# MCU_test.net
KiCad netlist of a schematic drawn in Altium Designer
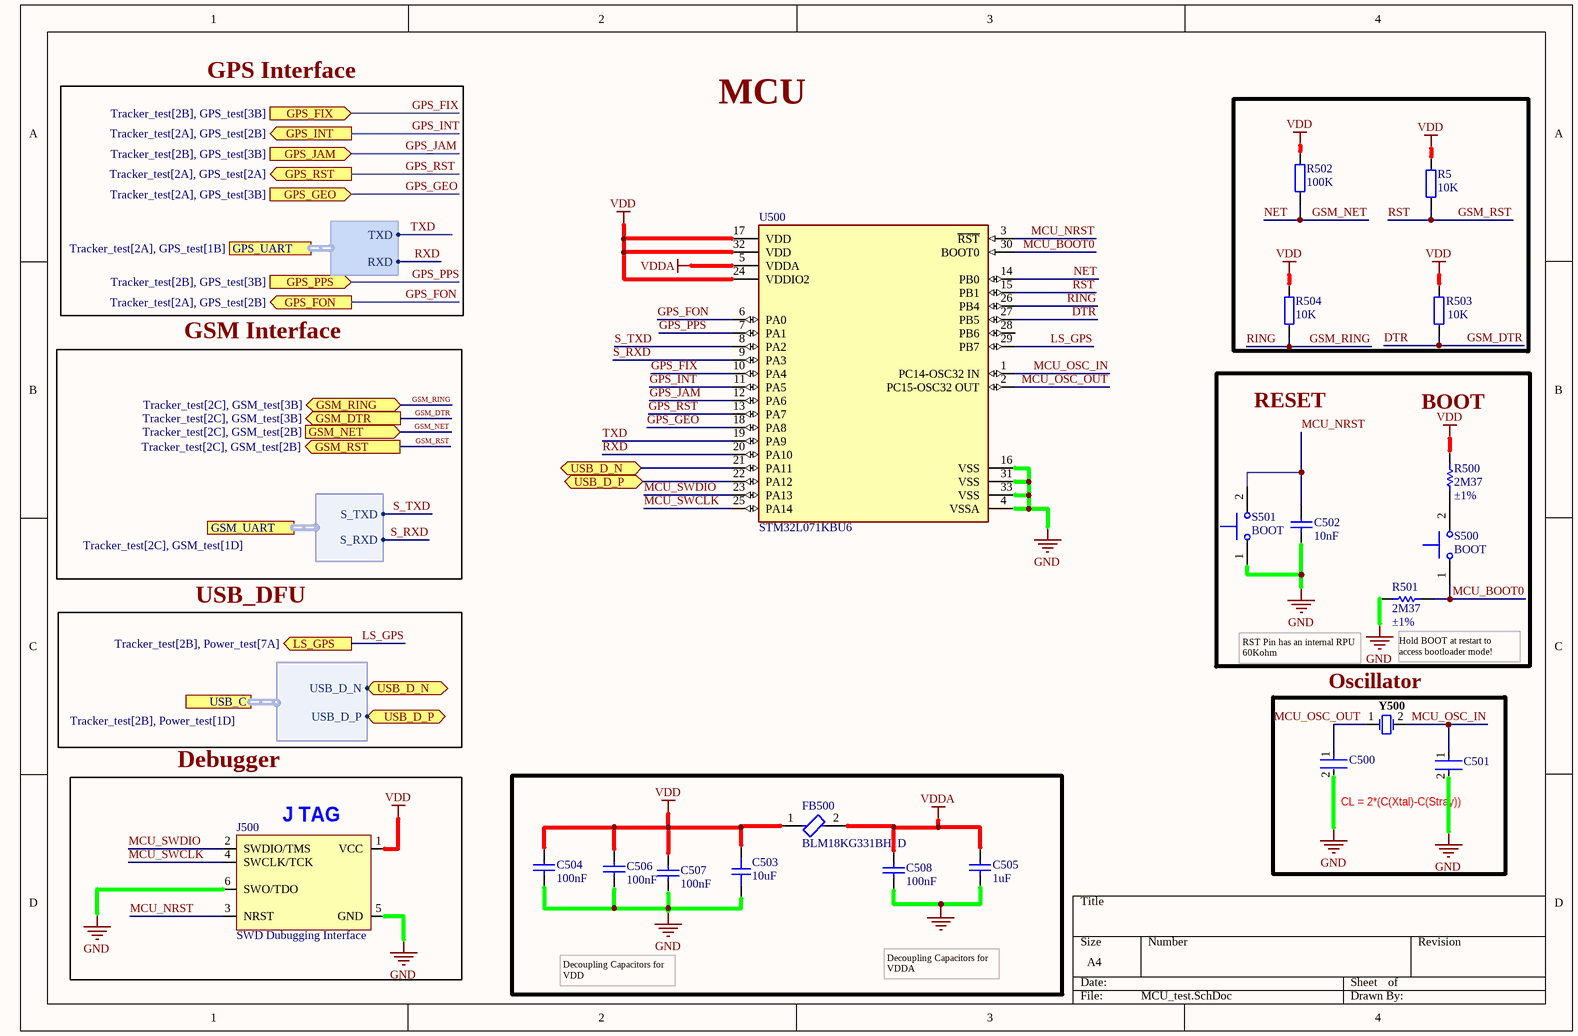
[diagram p0: MCU_test.SchDoc]

(export (version "E")
  (design (tool "Eeschema 10.0.6"))
  (components
    (comp (ref "C500")
      (value "C0603C220K5RACAUTO")
      (footprint "FP-C0603C-CF-IPC_B")
      (description "Cap Ceramic 22pF 50V X7R 10% SMD 0603 125°C Punched Paper T/R")
      (fields (field (name "TOLERANCE") "0.1") (field (name "MANUFACTURER") "KEMET"))
      (libsource (lib "intrgrat_lib") (part "CMP-03020-018041-1"))
    )
    (comp (ref "C501")
      (value "C0603C220K5RACAUTO")
      (footprint "FP-C0603C-CF-IPC_B")
      (description "Cap Ceramic 22pF 50V X7R 10% SMD 0603 125°C Punched Paper T/R")
      (fields (field (name "TOLERANCE") "0.1") (field (name "MANUFACTURER") "KEMET"))
      (libsource (lib "intrgrat_lib") (part "CMP-03020-018041-1"))
    )
    (comp (ref "C502")
      (value "10nF")
      (footprint "C0402 - duplicate")
      (description "CAP CER 0.1UF 10V X7R 0603")
      (fields
        (field (name "PART NUMBER") "C00062")
        (field (name "MANUFACTURER") "KEMET - Electronic Component")
      )
      (libsource (lib "intrgrat_lib") (part "CAP"))
    )
    (comp (ref "C503")
      (value "10uF")
      (footprint "CAP_0402")
      (description "Capacitor SMD 0402")
      (libsource (lib "PhilsLab_Library") (part "CAP_0402"))
    )
    (comp (ref "C504")
      (value "100nF")
      (footprint "C0402 - duplicate")
      (description "CAP CER 0.1UF 10V X7R 0603")
      (fields
        (field (name "PART NUMBER") "C00062")
        (field (name "MANUFACTURER") "KEMET - Electronic Component")
      )
      (libsource (lib "intrgrat_lib") (part "CAP"))
    )
    (comp (ref "C505")
      (value "1uF")
      (footprint "C0402 - duplicate")
      (description "CAP CER 0.1UF 10V X7R 0603")
      (fields
        (field (name "PART NUMBER") "C00062")
        (field (name "MANUFACTURER") "KEMET - Electronic Component")
      )
      (libsource (lib "intrgrat_lib") (part "CAP"))
    )
    (comp (ref "C506")
      (value "100nF")
      (footprint "C0402 - duplicate")
      (description "CAP CER 0.1UF 10V X7R 0603")
      (fields
        (field (name "PART NUMBER") "C00062")
        (field (name "MANUFACTURER") "KEMET - Electronic Component")
      )
      (libsource (lib "intrgrat_lib") (part "CAP"))
    )
    (comp (ref "C507")
      (value "100nF")
      (footprint "C0402 - duplicate")
      (description "CAP CER 0.1UF 10V X7R 0603")
      (fields
        (field (name "PART NUMBER") "C00062")
        (field (name "MANUFACTURER") "KEMET - Electronic Component")
      )
      (libsource (lib "intrgrat_lib") (part "CAP"))
    )
    (comp (ref "C508")
      (value "100nF")
      (footprint "C0402 - duplicate")
      (description "CAP CER 0.1UF 10V X7R 0603")
      (fields
        (field (name "PART NUMBER") "C00062")
        (field (name "MANUFACTURER") "KEMET - Electronic Component")
      )
      (libsource (lib "intrgrat_lib") (part "CAP"))
    )
    (comp (ref "FB500")
      (value "BLM18KG331BH1D")
      (footprint "FP-BLM18-0_15-t0_8-IPC_A")
      (description "Chip Ferrite Bead, 0603, 330Ω @ 100MHz, 0.08Ω, 25%, 1.2A")
      (libsource (lib "intrgrat_lib") (part "CMP-06046-002312-1"))
    )
    (comp (ref "J500")
      (value "SWD Dubugging Interface")
      (footprint "TC2030-NL-FP")
      (description "Tag-Connect No-Solder SWD Debug Connector (No Legs) DO NOT PLACE")
      (fields
        (field (name "MANUFACTURER") "Tag-Connect")
        (field (name "MANUFACTURER PART NUMBER") "TC2030-NL-FP")
      )
      (libsource (lib "intrgrat_lib") (part "TC2030-NL"))
    )
    (comp (ref "R5")
      (value "10K")
      (footprint "RES_0402")
      (description "Resistor SMD 0402")
      (libsource (lib "PhilsLab_Library") (part "RES_0402"))
    )
    (comp (ref "R500")
      (value "2M37")
      (footprint "R0402")
      (description "RES SMD 15 OHM 1% 1/10W 0603")
      (fields
        (field (name "PART NUMBER") "R00007")
        (field (name "MANUFACTURER") "Yageo")
        (field (name "TOLERANCE") "±1%")
      )
      (libsource (lib "intrgrat_lib") (part "RES"))
    )
    (comp (ref "R501")
      (value "2M37")
      (footprint "R0402")
      (description "RES SMD 15 OHM 1% 1/10W 0603")
      (fields
        (field (name "PART NUMBER") "R00007")
        (field (name "MANUFACTURER") "Yageo")
        (field (name "TOLERANCE") "±1%")
      )
      (libsource (lib "intrgrat_lib") (part "RES"))
    )
    (comp (ref "R502")
      (value "100K")
      (footprint "RES_0402")
      (description "Resistor SMD 0402")
      (libsource (lib "PhilsLab_Library") (part "RES_0402"))
    )
    (comp (ref "R503")
      (value "10K")
      (footprint "RES_0402")
      (description "Resistor SMD 0402")
      (libsource (lib "PhilsLab_Library") (part "RES_0402"))
    )
    (comp (ref "R504")
      (value "10K")
      (footprint "RES_0402")
      (description "Resistor SMD 0402")
      (libsource (lib "PhilsLab_Library") (part "RES_0402"))
    )
    (comp (ref "S500")
      (value "BOOT")
      (footprint "SW_B3U-1000P")
      (description "SWITCH TACTILE SPST-NO 0.05A 12V")
      (fields
        (field (name "PARTNUMBER") "B3U-1000P")
        (field (name "MANUFACTURER") "Omron Electronic Components")
        (field (name "SYMBOLCREATOR") "a0412235")
        (field (name "PUBLISHER") "Texas Instruments")
      )
      (libsource (lib "intrgrat_lib") (part "B3U-1000P"))
    )
    (comp (ref "S501")
      (value "BOOT")
      (footprint "SW_B3U-1000P")
      (description "SWITCH TACTILE SPST-NO 0.05A 12V")
      (fields
        (field (name "PARTNUMBER") "B3U-1000P")
        (field (name "MANUFACTURER") "Omron Electronic Components")
        (field (name "SYMBOLCREATOR") "a0412235")
        (field (name "PUBLISHER") "Texas Instruments")
      )
      (libsource (lib "intrgrat_lib") (part "B3U-1000P"))
    )
    (comp (ref "U500")
      (value "STM32L071KBU6")
      (footprint "FP-UFQFPN32-A0B8-IPC_B")
      (description "IC MCU 32BIT 128KB FLASH 32QFPN")
      (fields
        (field (name "OCTOPART") "https://octopart.com/stm32l071kbu6-stmicroelectronics-67270308")
        (field (name "MANUFACTURER") "STMicroelectronics")
      )
      (libsource (lib "intrgrat_lib") (part "CMP-12105-000059-1"))
    )
    (comp (ref "Y500")
      (value "NX3225GD-8MHZ-STD-CRA-3")
      (footprint "NDK-NX3225GD-8MHZ-STD-CRA-3_V")
      (description "Crystal Unit, 8 MHz, 8 pF, -40 to 150 degC, 2-Pin SMD, RoHS, Tape and Reel")
      (fields (field (name "MANUFACTURER") "NDK"))
      (libsource (lib "intrgrat_lib") (part "CMP-2000-07595-1"))
    )
  )
  (nets
    (net (code "4") (name "/DTR") (class "Default")
      (node (ref "R503") (pin "1") (pinfunction "1_1") (pintype "passive"))
      (node (ref "U500") (pin "27") (pinfunction "PB5_27") (pintype "bidirectional"))
    )
    (net (code "5") (name "/GPS_FIX") (class "Default")
      (node (ref "U500") (pin "10") (pinfunction "PA4_10") (pintype "bidirectional"))
    )
    (net (code "6") (name "/GPS_FON") (class "Default")
      (node (ref "U500") (pin "6") (pinfunction "PA0_6") (pintype "bidirectional"))
    )
    (net (code "7") (name "/GPS_GEO") (class "Default")
      (node (ref "U500") (pin "18") (pinfunction "PA8_18") (pintype "bidirectional"))
    )
    (net (code "8") (name "/GPS_INT") (class "Default")
      (node (ref "U500") (pin "11") (pinfunction "PA5_11") (pintype "bidirectional"))
    )
    (net (code "9") (name "/GPS_JAM") (class "Default")
      (node (ref "U500") (pin "12") (pinfunction "PA6_12") (pintype "bidirectional"))
    )
    (net (code "10") (name "/GPS_PPS") (class "Default")
      (node (ref "U500") (pin "7") (pinfunction "PA1_7") (pintype "bidirectional"))
    )
    (net (code "11") (name "/GPS_RST") (class "Default")
      (node (ref "U500") (pin "13") (pinfunction "PA7_13") (pintype "bidirectional"))
    )
    (net (code "12") (name "/GSM_NET") (class "Default")
      (node (ref "R502") (pin "2") (pinfunction "2_2") (pintype "passive"))
      (node (ref "U500") (pin "14") (pinfunction "PB0_14") (pintype "bidirectional"))
    )
    (net (code "13") (name "/GSM_RING") (class "Default")
      (node (ref "R504") (pin "2") (pinfunction "2_2") (pintype "passive"))
      (node (ref "U500") (pin "26") (pinfunction "PB4_26") (pintype "bidirectional"))
    )
    (net (code "14") (name "/GSM_RST") (class "Default")
      (node (ref "R5") (pin "2") (pinfunction "2_2") (pintype "passive"))
      (node (ref "U500") (pin "15") (pinfunction "PB1_15") (pintype "bidirectional"))
    )
    (net (code "15") (name "/LS_GPS") (class "Default")
      (node (ref "U500") (pin "29") (pinfunction "PB7_29") (pintype "bidirectional"))
    )
    (net (code "16") (name "/MCU_BOOT0") (class "Default")
      (node (ref "R501") (pin "2") (pinfunction "2_2") (pintype "passive"))
      (node (ref "S500") (pin "1") (pinfunction "1_1") (pintype "passive"))
      (node (ref "U500") (pin "30") (pinfunction "BOOT0_30") (pintype "input"))
    )
    (net (code "17") (name "/MCU_NRST") (class "Default")
      (node (ref "C502") (pin "1") (pinfunction "1_1") (pintype "passive"))
      (node (ref "J500") (pin "3") (pinfunction "NRST_3") (pintype "passive"))
      (node (ref "S501") (pin "2") (pinfunction "2_2") (pintype "passive"))
      (node (ref "U500") (pin "3") (pinfunction "~{RST}_3") (pintype "input"))
    )
    (net (code "18") (name "/MCU_OSC_IN") (class "Default")
      (node (ref "C501") (pin "1") (pinfunction "1_1") (pintype "passive"))
      (node (ref "U500") (pin "1") (pinfunction "PC14-OSC32_IN_1") (pintype "bidirectional"))
      (node (ref "Y500") (pin "2") (pinfunction "2_2") (pintype "passive"))
    )
    (net (code "19") (name "/MCU_OSC_OUT") (class "Default")
      (node (ref "C500") (pin "1") (pinfunction "1_1") (pintype "passive"))
      (node (ref "U500") (pin "2") (pinfunction "PC15-OSC32_OUT_2") (pintype "bidirectional"))
      (node (ref "Y500") (pin "1") (pinfunction "1_1") (pintype "passive"))
    )
    (net (code "20") (name "/MCU_SWCLK") (class "Default")
      (node (ref "J500") (pin "4") (pinfunction "SWCLK/TCK_4") (pintype "passive"))
      (node (ref "U500") (pin "25") (pinfunction "PA14_25") (pintype "bidirectional"))
    )
    (net (code "21") (name "/MCU_SWDIO") (class "Default")
      (node (ref "J500") (pin "2") (pinfunction "SWDIO/TMS_2") (pintype "passive"))
      (node (ref "U500") (pin "23") (pinfunction "PA13_23") (pintype "bidirectional"))
    )
    (net (code "22") (name "/RXD") (class "Default")
      (node (ref "U500") (pin "20") (pinfunction "PA10_20") (pintype "bidirectional"))
    )
    (net (code "23") (name "/S_RXD") (class "Default")
      (node (ref "U500") (pin "9") (pinfunction "PA3_9") (pintype "bidirectional"))
    )
    (net (code "24") (name "/S_TXD") (class "Default")
      (node (ref "U500") (pin "8") (pinfunction "PA2_8") (pintype "bidirectional"))
    )
    (net (code "25") (name "/TXD") (class "Default")
      (node (ref "U500") (pin "19") (pinfunction "PA9_19") (pintype "bidirectional"))
    )
    (net (code "26") (name "/USB_D_N") (class "Default")
      (node (ref "U500") (pin "21") (pinfunction "PA11_21") (pintype "bidirectional"))
    )
    (net (code "27") (name "/USB_D_P") (class "Default")
      (node (ref "U500") (pin "22") (pinfunction "PA12_22") (pintype "bidirectional"))
    )
    (net (code "31") (name "GND") (class "Default")
      (node (ref "C500") (pin "2") (pinfunction "2_2") (pintype "passive"))
      (node (ref "C501") (pin "2") (pinfunction "2_2") (pintype "passive"))
      (node (ref "C502") (pin "2") (pinfunction "2_2") (pintype "passive"))
      (node (ref "C503") (pin "1") (pinfunction "1_1") (pintype "passive"))
      (node (ref "C504") (pin "2") (pinfunction "2_2") (pintype "passive"))
      (node (ref "C505") (pin "2") (pinfunction "2_2") (pintype "passive"))
      (node (ref "C506") (pin "2") (pinfunction "2_2") (pintype "passive"))
      (node (ref "C507") (pin "2") (pinfunction "2_2") (pintype "passive"))
      (node (ref "C508") (pin "2") (pinfunction "2_2") (pintype "passive"))
      (node (ref "J500") (pin "5") (pinfunction "GND_5") (pintype "passive"))
      (node (ref "J500") (pin "6") (pinfunction "SWO/TDO_6") (pintype "passive"))
      (node (ref "R501") (pin "1") (pinfunction "1_1") (pintype "passive"))
      (node (ref "S501") (pin "1") (pinfunction "1_1") (pintype "passive"))
      (node (ref "U500") (pin "16") (pinfunction "VSS_16") (pintype "power_in"))
      (node (ref "U500") (pin "31") (pinfunction "VSS_31") (pintype "power_in"))
      (node (ref "U500") (pin "33") (pinfunction "VSS_33") (pintype "power_in"))
      (node (ref "U500") (pin "4") (pinfunction "VSSA_4") (pintype "power_in"))
    )
    (net (code "32") (name "Net-(R500-Pad2)") (class "Default")
      (node (ref "R500") (pin "2") (pinfunction "2_2") (pintype "passive"))
      (node (ref "S500") (pin "2") (pinfunction "2_2") (pintype "passive"))
    )
    (net (code "33") (name "VDD") (class "Default")
      (node (ref "C503") (pin "2") (pinfunction "2_2") (pintype "passive"))
      (node (ref "C504") (pin "1") (pinfunction "1_1") (pintype "passive"))
      (node (ref "C506") (pin "1") (pinfunction "1_1") (pintype "passive"))
      (node (ref "C507") (pin "1") (pinfunction "1_1") (pintype "passive"))
      (node (ref "FB500") (pin "1") (pinfunction "1_1") (pintype "passive"))
      (node (ref "J500") (pin "1") (pinfunction "VCC_1") (pintype "passive"))
      (node (ref "R5") (pin "1") (pinfunction "1_1") (pintype "passive"))
      (node (ref "R500") (pin "1") (pinfunction "1_1") (pintype "passive"))
      (node (ref "R502") (pin "1") (pinfunction "1_1") (pintype "passive"))
      (node (ref "R503") (pin "2") (pinfunction "2_2") (pintype "passive"))
      (node (ref "R504") (pin "1") (pinfunction "1_1") (pintype "passive"))
      (node (ref "U500") (pin "17") (pinfunction "VDD_17") (pintype "power_in"))
      (node (ref "U500") (pin "24") (pinfunction "VDDIO2_24") (pintype "power_in"))
      (node (ref "U500") (pin "32") (pinfunction "VDD_32") (pintype "power_in"))
    )
    (net (code "34") (name "VDDA") (class "Default")
      (node (ref "C505") (pin "1") (pinfunction "1_1") (pintype "passive"))
      (node (ref "C508") (pin "1") (pinfunction "1_1") (pintype "passive"))
      (node (ref "FB500") (pin "2") (pinfunction "2_2") (pintype "passive"))
      (node (ref "U500") (pin "5") (pinfunction "VDDA_5") (pintype "power_in"))
    )
    (net (code "35") (name "unconnected-(U500-PB6-Pad28)") (class "Default")
      (node (ref "U500") (pin "28") (pinfunction "PB6_28") (pintype "bidirectional"))
    )
  )
)
